# 2_IDC_Terminal.net
KiCad netlist of a schematic drawn in Altium Designer
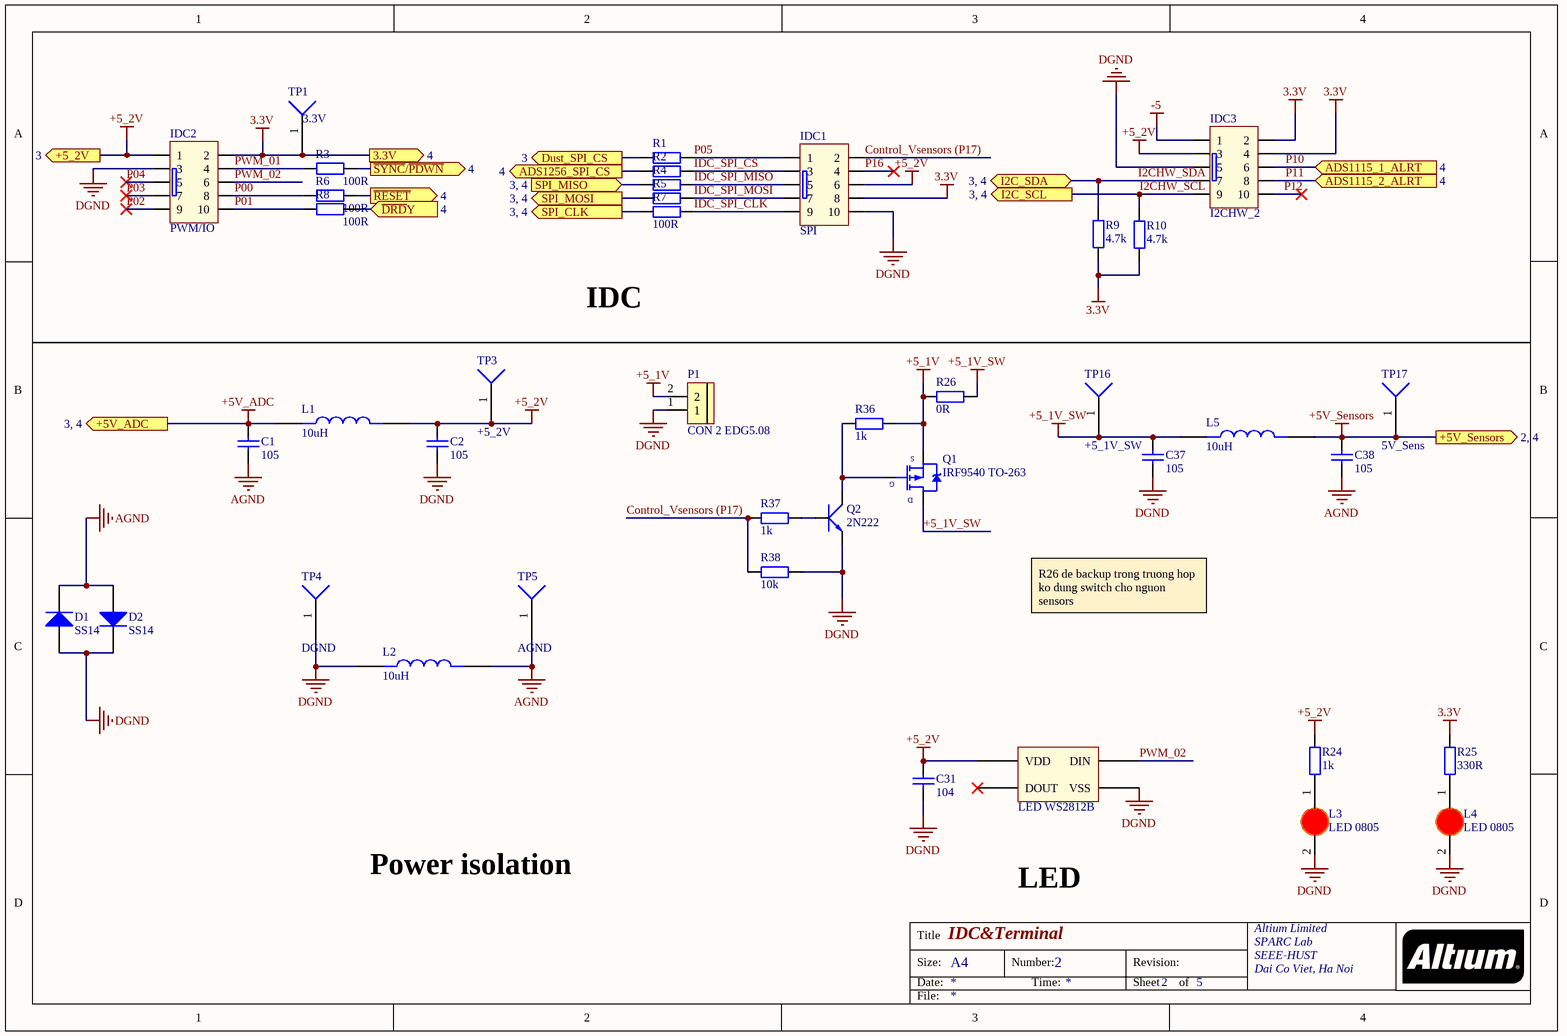
[diagram p0: [2]IDC_Terminal.SchDoc]

(export (version "E")
  (design (tool "Eeschema 10.0.6"))
  (components
    (comp (ref "C1")
      (value "105")
      (footprint "tu 0805")
      (description "Dán")
      (libsource (lib "Tu dien") (part "Tu 0805 105 50V 10%"))
    )
    (comp (ref "C2")
      (value "105")
      (footprint "tu 0805")
      (description "Dán")
      (libsource (lib "Tu dien") (part "Tu 0805 105 50V 10%"))
    )
    (comp (ref "C31")
      (value "104")
      (footprint "tu 0805")
      (description "Dán")
      (libsource (lib "Tu dien") (part "Tu 0805 104 50V 10%"))
    )
    (comp (ref "C37")
      (value "105")
      (footprint "tu 0805")
      (description "Dán")
      (libsource (lib "Tu dien") (part "Tu 0805 105 50V 10%"))
    )
    (comp (ref "C38")
      (value "105")
      (footprint "tu 0805")
      (description "Dán")
      (libsource (lib "Tu dien") (part "Tu 0805 105 50V 10%"))
    )
    (comp (ref "D1")
      (value "SS14")
      (footprint "DIODE SMA")
      (description "Dán")
      (libsource (lib "Diode") (part "Diode SS14 ( 1N5819)"))
    )
    (comp (ref "D2")
      (value "SS14")
      (footprint "DIODE SMA")
      (description "Dán")
      (libsource (lib "Diode") (part "Diode SS14 ( 1N5819)"))
    )
    (comp (ref "IDC1") (value "SPI") (footprint "IDC10") (libsource (lib "LIBRARY") (part "IDC 5X2")))
    (comp (ref "IDC2") (value "PWM/IO") (footprint "IDC10") (libsource (lib "LIBRARY") (part "IDC 5X2")))
    (comp (ref "IDC3") (value "I2CHW_2") (footprint "IDC10") (libsource (lib "LIBRARY") (part "IDC 5X2")))
    (comp (ref "L1")
      (value "10uH")
      (footprint "Inductor 0805")
      (description "1.5ÂµH Unshielded Multilayer Inductor 700mA 220mOhm 0805 (2012 Metric)")
      (fields (field (name "MF") "Laird") (field (name "MP") "CPI0805G1R5R-10"))
      (libsource (lib "Cuon Cam") (part "Cuon cam 0805"))
    )
    (comp (ref "L2")
      (value "10uH")
      (footprint "Inductor 0805")
      (description "1.5ÂµH Unshielded Multilayer Inductor 700mA 220mOhm 0805 (2012 Metric)")
      (fields (field (name "MF") "Laird") (field (name "MP") "CPI0805G1R5R-10"))
      (libsource (lib "Cuon Cam") (part "Cuon cam 0805"))
    )
    (comp (ref "L3")
      (value "LED 0805")
      (footprint "Led:LED-0805-Red")
      (description "Dán")
      (libsource (lib "Led") (part "LED 0805 Do"))
    )
    (comp (ref "L4")
      (value "LED 0805")
      (footprint "Led:LED-0805-Red")
      (description "Dán")
      (libsource (lib "Led") (part "LED 0805 Do"))
    )
    (comp (ref "L5")
      (value "10uH")
      (footprint "Inductor 0805")
      (description "1.5ÂµH Unshielded Multilayer Inductor 700mA 220mOhm 0805 (2012 Metric)")
      (fields (field (name "MF") "Laird") (field (name "MP") "CPI0805G1R5R-10"))
      (libsource (lib "") (part "Cuon cam 0805_1"))
    )
    (comp (ref "LED WS2812B")
      (value "LED WS2812B")
      (footprint "Led:LED-WS2812B")
      (libsource (lib "Led") (part "LED WS2812B"))
    )
    (comp (ref "P1")
      (value "CON 2 EDG5.08")
      (footprint "CON 2 2EDG5.08")
      (description "Cắm")
      (libsource (lib "Connector") (part "CON 2 EDG5.08"))
    )
    (comp (ref "Q1")
      (value "IRF9540 TO-263")
      (footprint "IC:TO-263-3_MOSFET")
      (description "P-Channel Power MOSFET")
      (fields (field (name "PUBLISHER") "Altium Limited"))
      (libsource (lib "TranFet") (part "IRF9540 SMD"))
    )
    (comp (ref "Q2")
      (value "2N222")
      (footprint "SOT23-231")
      (description "NPN 600mW, ECB")
      (libsource (lib "LIBRARY") (part "2N222"))
    )
    (comp (ref "R1")
      (value "100R")
      (footprint "tro smd 0805")
      (description "Dán")
      (libsource (lib "Dien Tro") (part "Tro 0805 5% 100R"))
    )
    (comp (ref "R2")
      (value "100R")
      (footprint "tro smd 0805")
      (description "Dán")
      (libsource (lib "Dien Tro") (part "Tro 0805 5% 100R"))
    )
    (comp (ref "R3")
      (value "100R")
      (footprint "tro smd 0805")
      (description "Dán")
      (libsource (lib "Dien Tro") (part "Tro 0805 5% 100R"))
    )
    (comp (ref "R4")
      (value "100R")
      (footprint "tro smd 0805")
      (description "Dán")
      (libsource (lib "Dien Tro") (part "Tro 0805 5% 100R"))
    )
    (comp (ref "R5")
      (value "100R")
      (footprint "tro smd 0805")
      (description "Dán")
      (libsource (lib "Dien Tro") (part "Tro 0805 5% 100R"))
    )
    (comp (ref "R6")
      (value "100R")
      (footprint "tro smd 0805")
      (description "Dán")
      (libsource (lib "Dien Tro") (part "Tro 0805 5% 100R"))
    )
    (comp (ref "R7")
      (value "100R")
      (footprint "tro smd 0805")
      (description "Dán")
      (libsource (lib "Dien Tro") (part "Tro 0805 5% 100R"))
    )
    (comp (ref "R8")
      (value "100R")
      (footprint "tro smd 0805")
      (description "Dán")
      (libsource (lib "Dien Tro") (part "Tro 0805 5% 100R"))
    )
    (comp (ref "R9")
      (value "4.7k")
      (footprint "tro smd 0805")
      (description "Dán")
      (libsource (lib "Dien Tro") (part "Tro 0805 5% 4.7k"))
    )
    (comp (ref "R10")
      (value "4.7k")
      (footprint "tro smd 0805")
      (description "Dán")
      (libsource (lib "Dien Tro") (part "Tro 0805 5% 4.7k"))
    )
    (comp (ref "R24")
      (value "1k")
      (footprint "tro smd 0805")
      (description "Dán")
      (libsource (lib "Dien Tro") (part "Tro 0805 5% 1k"))
    )
    (comp (ref "R25")
      (value "330R")
      (footprint "Tro SMD 0805")
      (description "Dán")
      (libsource (lib "Dien Tro") (part "Tro 0805 5% 330R"))
    )
    (comp (ref "R26")
      (value "0R")
      (footprint "tro smd 1206")
      (description "Dán")
      (libsource (lib "Dien Tro") (part "Tro 1206 5% 0R"))
    )
    (comp (ref "R36")
      (value "1k")
      (footprint "tro smd 0805")
      (description "Dán")
      (libsource (lib "Dien Tro") (part "Tro 0805 1% 1k"))
    )
    (comp (ref "R37")
      (value "1k")
      (footprint "tro smd 0805")
      (description "Dán")
      (libsource (lib "Dien Tro") (part "Tro 0805 1% 1k"))
    )
    (comp (ref "R38")
      (value "10k")
      (footprint "tro smd 0805")
      (description "Dán")
      (libsource (lib "Dien Tro") (part "Tro 0805 1% 10k"))
    )
    (comp (ref "TP1")
      (value "3.3V")
      (footprint "MinhTien_PCBLib:pad_1.65x1.65_hole_1mm")
      (description "Test Point")
      (fields (field (name "PUBLISHER") "Altium Limited"))
      (libsource (lib "MinhTien_SCHLib") (part "Test Point"))
    )
    (comp (ref "TP3")
      (value "+5_2V")
      (footprint "MinhTien_PCBLib:pad_1.65x1.65_hole_1mm")
      (description "Test Point")
      (fields (field (name "PUBLISHER") "Altium Limited"))
      (libsource (lib "MinhTien_SCHLib") (part "Test Point"))
    )
    (comp (ref "TP4")
      (value "DGND")
      (footprint "MinhTien_PCBLib:pad_1.65x1.65_hole_1mm")
      (description "Test Point")
      (fields (field (name "PUBLISHER") "Altium Limited"))
      (libsource (lib "MinhTien_SCHLib") (part "Test Point"))
    )
    (comp (ref "TP5")
      (value "AGND")
      (footprint "MinhTien_PCBLib:pad_1.65x1.65_hole_1mm")
      (description "Test Point")
      (fields (field (name "PUBLISHER") "Altium Limited"))
      (libsource (lib "MinhTien_SCHLib") (part "Test Point"))
    )
    (comp (ref "TP16")
      (value "+5_1V_SW")
      (footprint "MinhTien_PCBLib:pad_1.65x1.65_hole_1mm")
      (description "Test Point")
      (fields (field (name "PUBLISHER") "Altium Limited"))
      (libsource (lib "MinhTien_SCHLib") (part "Test Point"))
    )
    (comp (ref "TP17")
      (value "5V_Sens")
      (footprint "MinhTien_PCBLib:pad_1.65x1.65_hole_1mm")
      (description "Test Point")
      (fields (field (name "PUBLISHER") "Altium Limited"))
      (libsource (lib "MinhTien_SCHLib") (part "Test Point"))
    )
  )
  (nets
    (net (code "1") (name "+5V_ADC") (class "Default")
      (node (ref "C1") (pin "1") (pinfunction "1_1") (pintype "passive"))
      (node (ref "L1") (pin "1") (pinfunction "1_1") (pintype "passive"))
    )
    (net (code "2") (name "+5V_Sensors") (class "Default")
      (node (ref "C38") (pin "1") (pinfunction "1_1") (pintype "passive"))
      (node (ref "L5") (pin "1") (pinfunction "1_1") (pintype "passive"))
      (node (ref "TP17") (pin "1") (pinfunction "1_1") (pintype "passive"))
    )
    (net (code "3") (name "+5_1V") (class "Default")
      (node (ref "P1") (pin "2") (pinfunction "2_2") (pintype "passive"))
      (node (ref "Q1") (pin "3") (pinfunction "S_3") (pintype "passive"))
      (node (ref "R26") (pin "1") (pinfunction "1_1") (pintype "passive"))
      (node (ref "R36") (pin "2") (pinfunction "2_2") (pintype "passive"))
    )
    (net (code "4") (name "+5_1V_SW") (class "Default")
      (node (ref "C37") (pin "1") (pinfunction "1_1") (pintype "passive"))
      (node (ref "L5") (pin "2") (pinfunction "2_2") (pintype "passive"))
      (node (ref "Q1") (pin "2") (pinfunction "D_2") (pintype "passive"))
      (node (ref "R26") (pin "2") (pinfunction "2_2") (pintype "passive"))
      (node (ref "TP16") (pin "1") (pinfunction "1_1") (pintype "passive"))
    )
    (net (code "5") (name "+5_2V") (class "Default")
      (node (ref "C2") (pin "1") (pinfunction "1_1") (pintype "passive"))
      (node (ref "C31") (pin "1") (pinfunction "1_1") (pintype "passive"))
      (node (ref "IDC1") (pin "6") (pinfunction "6_6") (pintype "passive"))
      (node (ref "IDC2") (pin "1") (pinfunction "1_1") (pintype "passive"))
      (node (ref "IDC3") (pin "3") (pinfunction "3_3") (pintype "passive"))
      (node (ref "L1") (pin "2") (pinfunction "2_2") (pintype "passive"))
      (node (ref "LED WS2812B") (pin "1-VDD") (pinfunction "VDD_1-VDD") (pintype "passive"))
      (node (ref "R24") (pin "1") (pinfunction "1_1") (pintype "passive"))
      (node (ref "TP3") (pin "1") (pinfunction "1_1") (pintype "passive"))
    )
    (net (code "6") (name "-5") (class "Default")
      (node (ref "IDC3") (pin "1") (pinfunction "1_1") (pintype "passive"))
    )
    (net (code "7") (name "/ADS1256_SPI_CS") (class "Default")
      (node (ref "R2") (pin "1") (pinfunction "1_1") (pintype "passive"))
    )
    (net (code "8") (name "/Control_Vsensors (P17)") (class "Default")
      (node (ref "IDC1") (pin "2") (pinfunction "2_2") (pintype "passive"))
      (node (ref "R37") (pin "1") (pinfunction "1_1") (pintype "passive"))
      (node (ref "R38") (pin "1") (pinfunction "1_1") (pintype "passive"))
    )
    (net (code "9") (name "/Dust_SPI_CS") (class "Default")
      (node (ref "R1") (pin "1") (pinfunction "1_1") (pintype "passive"))
    )
    (net (code "10") (name "/I2CHW_SCL") (class "Default")
      (node (ref "IDC3") (pin "9") (pinfunction "9_9") (pintype "passive"))
      (node (ref "R10") (pin "2") (pinfunction "2_2") (pintype "passive"))
    )
    (net (code "11") (name "/I2CHW_SDA") (class "Default")
      (node (ref "IDC3") (pin "7") (pinfunction "7_7") (pintype "passive"))
      (node (ref "R9") (pin "2") (pinfunction "2_2") (pintype "passive"))
    )
    (net (code "12") (name "/IDC_SPI_CLK") (class "Default")
      (node (ref "IDC1") (pin "9") (pinfunction "9_9") (pintype "passive"))
      (node (ref "R7") (pin "2") (pinfunction "2_2") (pintype "passive"))
    )
    (net (code "13") (name "/IDC_SPI_CS") (class "Default")
      (node (ref "IDC1") (pin "3") (pinfunction "3_3") (pintype "passive"))
      (node (ref "R2") (pin "2") (pinfunction "2_2") (pintype "passive"))
    )
    (net (code "14") (name "/IDC_SPI_MISO") (class "Default")
      (node (ref "IDC1") (pin "5") (pinfunction "5_5") (pintype "passive"))
      (node (ref "R4") (pin "2") (pinfunction "2_2") (pintype "passive"))
    )
    (net (code "15") (name "/IDC_SPI_MOSI") (class "Default")
      (node (ref "IDC1") (pin "7") (pinfunction "7_7") (pintype "passive"))
      (node (ref "R5") (pin "2") (pinfunction "2_2") (pintype "passive"))
    )
    (net (code "16") (name "/P00") (class "Default")
      (node (ref "IDC2") (pin "8") (pinfunction "8_8") (pintype "passive"))
      (node (ref "R6") (pin "2") (pinfunction "2_2") (pintype "passive"))
    )
    (net (code "17") (name "/P01") (class "Default")
      (node (ref "IDC2") (pin "10") (pinfunction "10_10") (pintype "passive"))
      (node (ref "R8") (pin "2") (pinfunction "2_2") (pintype "passive"))
    )
    (net (code "18") (name "/P02") (class "Default")
      (node (ref "IDC2") (pin "9") (pinfunction "9_9") (pintype "passive+no_connect"))
    )
    (net (code "19") (name "/P03") (class "Default")
      (node (ref "IDC2") (pin "7") (pinfunction "7_7") (pintype "passive+no_connect"))
    )
    (net (code "20") (name "/P04") (class "Default")
      (node (ref "IDC2") (pin "5") (pinfunction "5_5") (pintype "passive+no_connect"))
    )
    (net (code "21") (name "/P05") (class "Default")
      (node (ref "IDC1") (pin "1") (pinfunction "1_1") (pintype "passive"))
      (node (ref "R1") (pin "2") (pinfunction "2_2") (pintype "passive"))
    )
    (net (code "22") (name "/P10") (class "Default")
      (node (ref "IDC3") (pin "6") (pinfunction "6_6") (pintype "passive"))
    )
    (net (code "23") (name "/P11") (class "Default")
      (node (ref "IDC3") (pin "8") (pinfunction "8_8") (pintype "passive"))
    )
    (net (code "24") (name "/P12") (class "Default")
      (node (ref "IDC3") (pin "10") (pinfunction "10_10") (pintype "passive+no_connect"))
    )
    (net (code "25") (name "/P16") (class "Default")
      (node (ref "IDC1") (pin "4") (pinfunction "4_4") (pintype "passive+no_connect"))
    )
    (net (code "26") (name "/PWM_01") (class "Default")
      (node (ref "IDC2") (pin "4") (pinfunction "4_4") (pintype "passive"))
      (node (ref "R3") (pin "2") (pinfunction "2_2") (pintype "passive"))
    )
    (net (code "27") (name "/PWM_02") (class "Default")
      (node (ref "IDC2") (pin "6") (pinfunction "6_6") (pintype "passive"))
      (node (ref "LED WS2812B") (pin "4-DIN") (pinfunction "DIN_4-DIN") (pintype "passive"))
    )
    (net (code "28") (name "/SPI_CLK") (class "Default")
      (node (ref "R7") (pin "1") (pinfunction "1_1") (pintype "passive"))
    )
    (net (code "29") (name "/SPI_MISO") (class "Default")
      (node (ref "R4") (pin "1") (pinfunction "1_1") (pintype "passive"))
    )
    (net (code "30") (name "/SPI_MOSI") (class "Default")
      (node (ref "R5") (pin "1") (pinfunction "1_1") (pintype "passive"))
    )
    (net (code "31") (name "/~{DRD}Y") (class "Default")
      (node (ref "R8") (pin "1") (pinfunction "1_1") (pintype "passive"))
    )
    (net (code "32") (name "/~{RESET}") (class "Default")
      (node (ref "R6") (pin "1") (pinfunction "1_1") (pintype "passive"))
    )
    (net (code "33") (name "/~{SYNC}{slash}~{PDWN}") (class "Default")
      (node (ref "R3") (pin "1") (pinfunction "1_1") (pintype "passive"))
    )
    (net (code "34") (name "3.3V") (class "Default")
      (node (ref "IDC1") (pin "8") (pinfunction "8_8") (pintype "passive"))
      (node (ref "IDC2") (pin "2") (pinfunction "2_2") (pintype "passive"))
      (node (ref "IDC3") (pin "2") (pinfunction "2_2") (pintype "passive"))
      (node (ref "IDC3") (pin "4") (pinfunction "4_4") (pintype "passive"))
      (node (ref "R10") (pin "1") (pinfunction "1_1") (pintype "passive"))
      (node (ref "R25") (pin "2") (pinfunction "2_2") (pintype "passive"))
      (node (ref "R9") (pin "1") (pinfunction "1_1") (pintype "passive"))
      (node (ref "TP1") (pin "1") (pinfunction "1_1") (pintype "passive"))
    )
    (net (code "35") (name "AGND") (class "Default")
      (node (ref "C1") (pin "2") (pinfunction "2_2") (pintype "passive"))
      (node (ref "C38") (pin "2") (pinfunction "2_2") (pintype "passive"))
      (node (ref "D1") (pin "2") (pinfunction "K_2") (pintype "passive"))
      (node (ref "D2") (pin "1") (pinfunction "A_1") (pintype "passive"))
      (node (ref "L2") (pin "2") (pinfunction "2_2") (pintype "passive"))
      (node (ref "TP5") (pin "1") (pinfunction "1_1") (pintype "passive"))
    )
    (net (code "36") (name "DGND") (class "Default")
      (node (ref "C2") (pin "2") (pinfunction "2_2") (pintype "passive"))
      (node (ref "C31") (pin "2") (pinfunction "2_2") (pintype "passive"))
      (node (ref "C37") (pin "2") (pinfunction "2_2") (pintype "passive"))
      (node (ref "D1") (pin "1") (pinfunction "A_1") (pintype "passive"))
      (node (ref "D2") (pin "2") (pinfunction "K_2") (pintype "passive"))
      (node (ref "IDC1") (pin "10") (pinfunction "10_10") (pintype "passive"))
      (node (ref "IDC2") (pin "3") (pinfunction "3_3") (pintype "passive"))
      (node (ref "IDC3") (pin "5") (pinfunction "5_5") (pintype "passive"))
      (node (ref "L2") (pin "1") (pinfunction "1_1") (pintype "passive"))
      (node (ref "L3") (pin "2") (pinfunction "K_2") (pintype "passive"))
      (node (ref "L4") (pin "2") (pinfunction "K_2") (pintype "passive"))
      (node (ref "LED WS2812B") (pin "3-GND") (pinfunction "VSS_3-GND") (pintype "passive"))
      (node (ref "P1") (pin "1") (pinfunction "1_1") (pintype "passive"))
      (node (ref "Q2") (pin "1") (pinfunction "E_1") (pintype "passive"))
      (node (ref "R38") (pin "2") (pinfunction "2_2") (pintype "passive"))
      (node (ref "TP4") (pin "1") (pinfunction "1_1") (pintype "passive"))
    )
    (net (code "37") (name "Net-(L3-A)") (class "Default")
      (node (ref "L3") (pin "1") (pinfunction "A_1") (pintype "passive"))
      (node (ref "R24") (pin "2") (pinfunction "2_2") (pintype "passive"))
    )
    (net (code "38") (name "Net-(L4-A)") (class "Default")
      (node (ref "L4") (pin "1") (pinfunction "A_1") (pintype "passive"))
      (node (ref "R25") (pin "1") (pinfunction "1_1") (pintype "passive"))
    )
    (net (code "39") (name "Net-(Q1-G)") (class "Default")
      (node (ref "Q1") (pin "1") (pinfunction "G_1") (pintype "passive"))
      (node (ref "Q2") (pin "3") (pinfunction "C_3") (pintype "passive"))
      (node (ref "R36") (pin "1") (pinfunction "1_1") (pintype "passive"))
    )
    (net (code "40") (name "Net-(Q2-B)") (class "Default")
      (node (ref "Q2") (pin "2") (pinfunction "B_2") (pintype "passive"))
      (node (ref "R37") (pin "2") (pinfunction "2_2") (pintype "passive"))
    )
    (net (code "41") (name "unconnected-(LED WS2812B-DOUT-Pad2-DOUT)") (class "Default")
      (node (ref "LED WS2812B") (pin "2-DOUT") (pinfunction "DOUT_2-DOUT") (pintype "passive+no_connect"))
    )
  )
)
